# 5V2_4A.net
KiCad netlist of a schematic drawn in Altium Designer
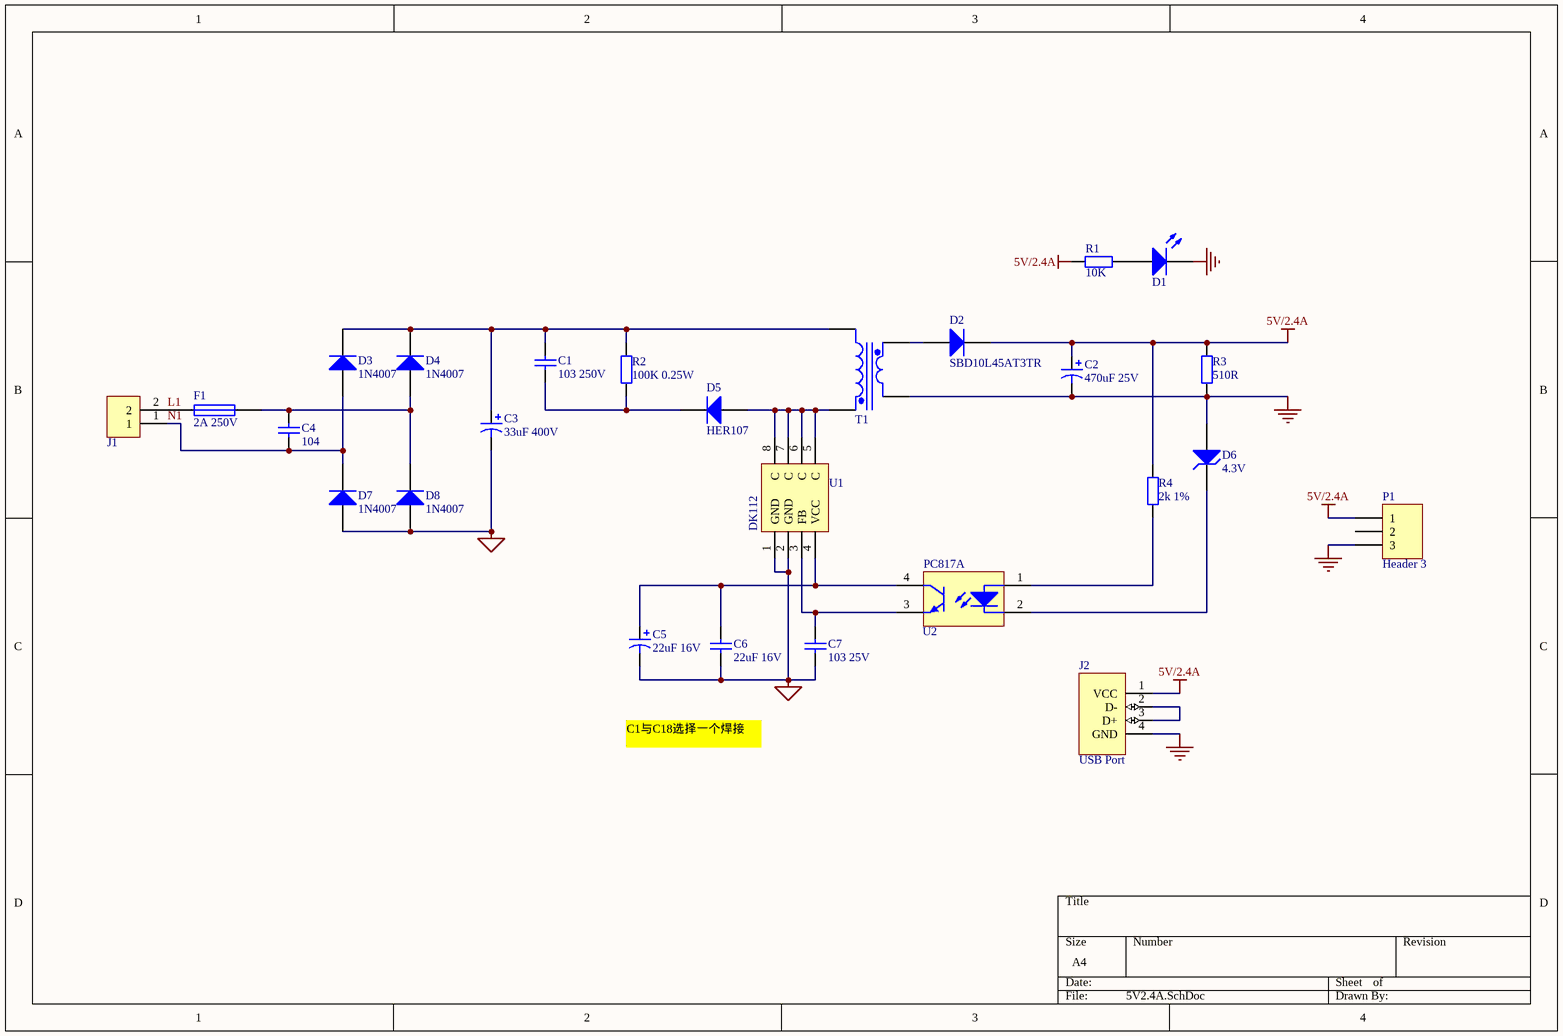
[diagram p0: 5V2.4A.SchDoc]

(export (version "E")
  (design (tool "Eeschema 10.0.6"))
  (components
    (comp (ref "C1")
      (value "103 250V")
      (footprint "DK112_DK1203验证板1:CAP_0805")
      (libsource (lib "钦的集成库1") (part "Cap_2"))
    )
    (comp (ref "C2")
      (value "470uF 25V")
      (footprint "DK112_DK1203验证板1:CAP POLL 直插电解质8*12/8*16")
      (libsource (lib "钦的集成库1") (part "Cap_"))
    )
    (comp (ref "C3")
      (value "33uF 400V")
      (footprint "DK112_DK1203验证板1:Cap POLL 直插电解质 13*20")
      (libsource (lib "钦的集成库1") (part "Cap_"))
    )
    (comp (ref "C4")
      (value "104")
      (footprint "DK112_DK1203验证板1:Cap安规104")
      (libsource (lib "钦的集成库1") (part "Cap_2"))
    )
    (comp (ref "C5")
      (value "22uF 16V")
      (footprint "DK112_DK1203验证板1:CAP POLL 直插电解质5*12")
      (libsource (lib "钦的集成库1") (part "Cap_"))
    )
    (comp (ref "C6")
      (value "22uF 16V")
      (footprint "DK112_DK1203验证板1:1210")
      (libsource (lib "钦的集成库1") (part "Cap_2"))
    )
    (comp (ref "C7")
      (value "103 25V")
      (footprint "DK112_DK1203验证板1:CAP瓷片直插")
      (libsource (lib "钦的集成库1") (part "Cap_2"))
    )
    (comp (ref "D1")
      (value "LED_")
      (footprint "DK112_DK1203验证板1:LED_0805")
      (libsource (lib "钦的集成库1") (part "LED_"))
    )
    (comp (ref "D2")
      (value "SBD10L45AT3TR")
      (footprint "DK112_DK1203验证板1:TO-277")
      (libsource (lib "钦的集成库1") (part "1N4007"))
    )
    (comp (ref "D3") (value "1N4007") (footprint "直插二极管") (libsource (lib "钦的原理图库1") (part "1N4007")))
    (comp (ref "D4") (value "1N4007") (footprint "直插二极管") (libsource (lib "钦的原理图库1") (part "1N4007")))
    (comp (ref "D5")
      (value "HER107")
      (footprint "DK112_DK1203验证板1:DO-41")
      (libsource (lib "钦的集成库1") (part "1N4007"))
    )
    (comp (ref "D6")
      (value "4.3V")
      (footprint "DK112_DK1203验证板1:LL-34")
      (libsource (lib "钦的集成库1") (part "稳压二极管"))
    )
    (comp (ref "D7") (value "1N4007") (footprint "直插二极管") (libsource (lib "钦的原理图库1") (part "1N4007")))
    (comp (ref "D8") (value "1N4007") (footprint "直插二极管") (libsource (lib "钦的原理图库1") (part "1N4007")))
    (comp (ref "F1")
      (value "Fuse")
      (footprint "DK112_DK1203验证板1:2410")
      (fields (field (name "I HOLD") "2A 250V"))
      (libsource (lib "钦的集成库1") (part "Fuse"))
    )
    (comp (ref "J1")
      (value "接线端子2P")
      (footprint "DK112_DK1203验证板1:接线端子2P")
      (libsource (lib "钦的集成库1") (part "接线端子2P"))
    )
    (comp (ref "J2")
      (value "USB Port")
      (footprint "DK112_DK1203验证板1:USB-A 母座 贴片")
      (libsource (lib "钦的集成库1") (part "USB Port"))
    )
    (comp (ref "P1")
      (value "Header 3")
      (footprint "HDR1X3")
      (description "Header, 3-Pin")
      (fields (field (name "PUBLISHER") "Altium Limited"))
      (libsource (lib "Miscellaneous Connectors") (part "Header 3"))
    )
    (comp (ref "R1") (value "10K") (footprint "Res_0805") (libsource (lib "") (part "Res__1")))
    (comp (ref "R2") (value "100K 0.25W") (footprint "1206") (libsource (lib "钦的集成库1") (part "Res_")))
    (comp (ref "R3") (value "510R") (footprint "Res_0805") (libsource (lib "钦的集成库1") (part "Res_")))
    (comp (ref "R4") (value "2k 1%") (footprint "Res_0805") (libsource (lib "钦的集成库1") (part "Res_")))
    (comp (ref "T1")
      (value "变压器-双边-8引脚")
      (footprint "变压器EE20-5_5-剪脚")
      (libsource (lib "钦的原理图库1") (part "变压器-双边-8引脚"))
    )
    (comp (ref "U1") (value "DK112") (footprint "DIP-8") (libsource (lib "钦的集成库1") (part "DK112")))
    (comp (ref "U2") (value "PC817A") (footprint "DIP-4") (libsource (lib "钦的原理图库1") (part "光耦 - 1")))
  )
  (nets
    (net (code "1") (name "/L1") (class "Default")
      (node (ref "F1") (pin "1") (pinfunction "1_1") (pintype "passive"))
      (node (ref "J1") (pin "2") (pinfunction "2_2") (pintype "power_in"))
    )
    (net (code "2") (name "/N1") (class "Default")
      (node (ref "C4") (pin "1") (pinfunction "1_1") (pintype "passive"))
      (node (ref "D3") (pin "1") (pinfunction "A_1") (pintype "passive"))
      (node (ref "D7") (pin "2") (pinfunction "K_2") (pintype "passive"))
      (node (ref "J1") (pin "1") (pinfunction "1_1") (pintype "power_in"))
    )
    (net (code "3") (name "5V{slash}2.4A") (class "Default")
      (node (ref "C2") (pin "1") (pinfunction "1_1") (pintype "passive"))
      (node (ref "D2") (pin "2") (pinfunction "K_2") (pintype "passive"))
      (node (ref "J2") (pin "1") (pinfunction "VCC_1") (pintype "power_in"))
      (node (ref "P1") (pin "1") (pinfunction "1_1") (pintype "passive"))
      (node (ref "R1") (pin "2") (pinfunction "2_2") (pintype "passive"))
      (node (ref "R3") (pin "2") (pinfunction "2_2") (pintype "passive"))
      (node (ref "R4") (pin "2") (pinfunction "2_2") (pintype "passive"))
    )
    (net (code "4") (name "GND1") (class "Default")
      (node (ref "C2") (pin "2") (pinfunction "2_2") (pintype "passive"))
      (node (ref "D1") (pin "2") (pinfunction "K_2") (pintype "passive"))
      (node (ref "D6") (pin "1") (pinfunction "A_1") (pintype "passive"))
      (node (ref "J2") (pin "4") (pinfunction "GND_4") (pintype "power_in"))
      (node (ref "P1") (pin "3") (pinfunction "3_3") (pintype "passive"))
      (node (ref "R3") (pin "1") (pinfunction "1_1") (pintype "passive"))
      (node (ref "T1") (pin "6") (pinfunction "Sec-_6") (pintype "passive"))
    )
    (net (code "5") (name "Net-(D1-A)") (class "Default")
      (node (ref "D1") (pin "1") (pinfunction "A_1") (pintype "passive"))
      (node (ref "R1") (pin "1") (pinfunction "1_1") (pintype "passive"))
    )
    (net (code "6") (name "Net-(D2-A)") (class "Default")
      (node (ref "D2") (pin "1") (pinfunction "A_1") (pintype "passive"))
      (node (ref "T1") (pin "7") (pinfunction "Sec+_7") (pintype "passive"))
    )
    (net (code "7") (name "Net-(D3-K)") (class "Default")
      (node (ref "C1") (pin "2") (pinfunction "2_2") (pintype "passive"))
      (node (ref "C3") (pin "1") (pinfunction "1_1") (pintype "passive"))
      (node (ref "D3") (pin "2") (pinfunction "K_2") (pintype "passive"))
      (node (ref "D4") (pin "2") (pinfunction "K_2") (pintype "passive"))
      (node (ref "R2") (pin "2") (pinfunction "2_2") (pintype "passive"))
      (node (ref "T1") (pin "1") (pinfunction "Pri+_1") (pintype "passive"))
    )
    (net (code "8") (name "Net-(D4-A)") (class "Default")
      (node (ref "C4") (pin "2") (pinfunction "2_2") (pintype "passive"))
      (node (ref "D4") (pin "1") (pinfunction "A_1") (pintype "passive"))
      (node (ref "D8") (pin "2") (pinfunction "K_2") (pintype "passive"))
      (node (ref "F1") (pin "2") (pinfunction "2_2") (pintype "passive"))
    )
    (net (code "9") (name "Net-(D5-A)") (class "Default")
      (node (ref "D5") (pin "1") (pinfunction "A_1") (pintype "passive"))
      (node (ref "T1") (pin "4") (pinfunction "Pri-_4") (pintype "passive"))
      (node (ref "U1") (pin "5") (pinfunction "C_5") (pintype "passive"))
      (node (ref "U1") (pin "6") (pinfunction "C_6") (pintype "passive"))
      (node (ref "U1") (pin "7") (pinfunction "C_7") (pintype "passive"))
      (node (ref "U1") (pin "8") (pinfunction "C_8") (pintype "passive"))
    )
    (net (code "10") (name "Net-(D5-K)") (class "Default")
      (node (ref "C1") (pin "1") (pinfunction "1_1") (pintype "passive"))
      (node (ref "D5") (pin "2") (pinfunction "K_2") (pintype "passive"))
      (node (ref "R2") (pin "1") (pinfunction "1_1") (pintype "passive"))
    )
    (net (code "11") (name "Net-(D6-K)") (class "Default")
      (node (ref "D6") (pin "2") (pinfunction "K_2") (pintype "passive"))
      (node (ref "U2") (pin "2") (pinfunction "K_2") (pintype "passive"))
    )
    (net (code "12") (name "Net-(J2-D+)") (class "Default")
      (node (ref "J2") (pin "2") (pinfunction "D-_2") (pintype "bidirectional"))
      (node (ref "J2") (pin "3") (pinfunction "D+_3") (pintype "bidirectional"))
    )
    (net (code "13") (name "Net-(U1-FB)") (class "Default")
      (node (ref "C7") (pin "2") (pinfunction "2_2") (pintype "passive"))
      (node (ref "U1") (pin "3") (pinfunction "FB_3") (pintype "passive"))
      (node (ref "U2") (pin "3") (pinfunction "E_3") (pintype "passive"))
    )
    (net (code "14") (name "Net-(U1-VCC)") (class "Default")
      (node (ref "C5") (pin "1") (pinfunction "1_1") (pintype "passive"))
      (node (ref "C6") (pin "2") (pinfunction "2_2") (pintype "passive"))
      (node (ref "U1") (pin "4") (pinfunction "VCC_4") (pintype "power_in"))
      (node (ref "U2") (pin "4") (pinfunction "C_4") (pintype "passive"))
    )
    (net (code "15") (name "Net-(U2-A)") (class "Default")
      (node (ref "R4") (pin "1") (pinfunction "1_1") (pintype "passive"))
      (node (ref "U2") (pin "1") (pinfunction "A_1") (pintype "passive"))
    )
    (net (code "16") (name "PGND1") (class "Default")
      (node (ref "C3") (pin "2") (pinfunction "2_2") (pintype "passive"))
      (node (ref "C5") (pin "2") (pinfunction "2_2") (pintype "passive"))
      (node (ref "C6") (pin "1") (pinfunction "1_1") (pintype "passive"))
      (node (ref "C7") (pin "1") (pinfunction "1_1") (pintype "passive"))
      (node (ref "D7") (pin "1") (pinfunction "A_1") (pintype "passive"))
      (node (ref "D8") (pin "1") (pinfunction "A_1") (pintype "passive"))
      (node (ref "U1") (pin "1") (pinfunction "GND_1") (pintype "power_in"))
      (node (ref "U1") (pin "2") (pinfunction "GND_2") (pintype "power_in"))
    )
    (net (code "17") (name "unconnected-(P1-Pad2)") (class "Default")
      (node (ref "P1") (pin "2") (pinfunction "2_2") (pintype "passive"))
    )
  )
)
